# AnalogDiscoveryJacks.net
KiCad netlist of a schematic drawn in EAGLE
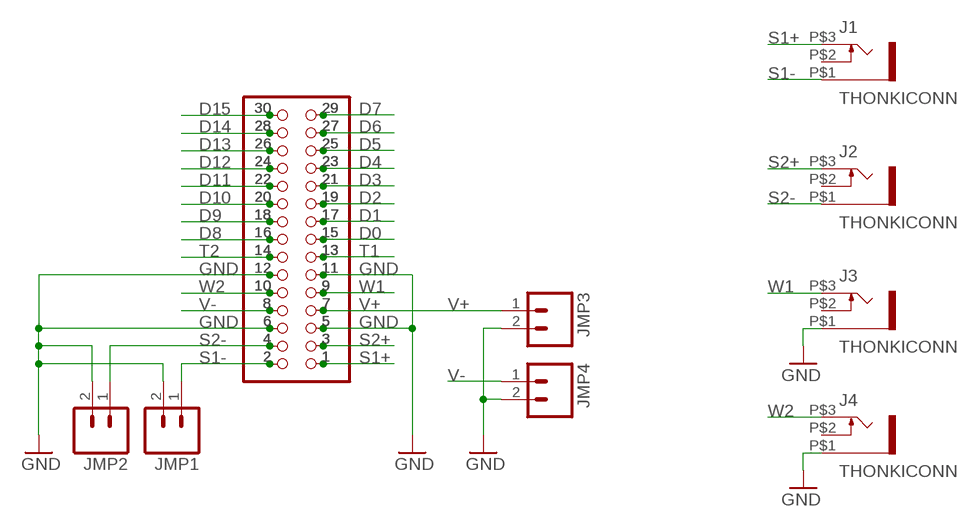
[diagram p0: schematic, sheet 1]

(export (version "E")
  (design (tool "Eeschema 10.0.6"))
  (components
    (comp (ref "J1")
      (value "THONKICONN")
      (footprint "eagle-import:THONKICONN")
      (libsource (lib "eagle-import") (part "THONKICONN"))
    )
    (comp (ref "J2")
      (value "THONKICONN")
      (footprint "eagle-import:THONKICONN")
      (libsource (lib "eagle-import") (part "THONKICONN"))
    )
    (comp (ref "J3")
      (value "THONKICONN")
      (footprint "eagle-import:THONKICONN")
      (libsource (lib "eagle-import") (part "THONKICONN"))
    )
    (comp (ref "J4")
      (value "THONKICONN")
      (footprint "eagle-import:THONKICONN")
      (libsource (lib "eagle-import") (part "THONKICONN"))
    )
    (comp (ref "JMP1")
      (value "M02PTH")
      (footprint "eagle-import:1X02")
      (libsource (lib "eagle-import") (part "M02PTH"))
    )
    (comp (ref "JMP2")
      (value "M02PTH")
      (footprint "eagle-import:1X02")
      (libsource (lib "eagle-import") (part "M02PTH"))
    )
    (comp (ref "JMP3")
      (value "M02PTH")
      (footprint "eagle-import:1X02")
      (libsource (lib "eagle-import") (part "M02PTH"))
    )
    (comp (ref "JMP4")
      (value "M02PTH")
      (footprint "eagle-import:1X02")
      (libsource (lib "eagle-import") (part "M02PTH"))
    )
    (comp (ref "JP1")
      (value "PINHD-2X15")
      (footprint "eagle-import:2X15")
      (libsource (lib "eagle-import") (part "PINHD-2X15"))
    )
    (comp (ref "JP2")
      (value "PINHD-2X15")
      (footprint "eagle-import:2X15")
      (libsource (lib "eagle-import") (part "PINHD-2X15"))
    )
    (comp (ref "JP3")
      (value "PINHD-2X15")
      (footprint "eagle-import:2X15")
      (libsource (lib "eagle-import") (part "PINHD-2X15"))
    )
  )
  (nets
    (net (code "1") (name "/D0") (class "Default")
      (node (ref "JP1") (pin "15") (pinfunction "15_15") (pintype "passive"))
      (node (ref "JP2") (pin "15") (pinfunction "15_15") (pintype "passive"))
      (node (ref "JP3") (pin "15") (pinfunction "15_15") (pintype "passive"))
    )
    (net (code "2") (name "/D1") (class "Default")
      (node (ref "JP1") (pin "17") (pinfunction "17_17") (pintype "passive"))
      (node (ref "JP2") (pin "17") (pinfunction "17_17") (pintype "passive"))
      (node (ref "JP3") (pin "17") (pinfunction "17_17") (pintype "passive"))
    )
    (net (code "3") (name "/D2") (class "Default")
      (node (ref "JP1") (pin "19") (pinfunction "19_19") (pintype "passive"))
      (node (ref "JP2") (pin "19") (pinfunction "19_19") (pintype "passive"))
      (node (ref "JP3") (pin "19") (pinfunction "19_19") (pintype "passive"))
    )
    (net (code "4") (name "/D3") (class "Default")
      (node (ref "JP1") (pin "21") (pinfunction "21_21") (pintype "passive"))
      (node (ref "JP2") (pin "21") (pinfunction "21_21") (pintype "passive"))
      (node (ref "JP3") (pin "21") (pinfunction "21_21") (pintype "passive"))
    )
    (net (code "5") (name "/D4") (class "Default")
      (node (ref "JP1") (pin "23") (pinfunction "23_23") (pintype "passive"))
      (node (ref "JP2") (pin "23") (pinfunction "23_23") (pintype "passive"))
      (node (ref "JP3") (pin "23") (pinfunction "23_23") (pintype "passive"))
    )
    (net (code "6") (name "/D5") (class "Default")
      (node (ref "JP1") (pin "25") (pinfunction "25_25") (pintype "passive"))
      (node (ref "JP2") (pin "25") (pinfunction "25_25") (pintype "passive"))
      (node (ref "JP3") (pin "25") (pinfunction "25_25") (pintype "passive"))
    )
    (net (code "7") (name "/D6") (class "Default")
      (node (ref "JP1") (pin "27") (pinfunction "27_27") (pintype "passive"))
      (node (ref "JP2") (pin "27") (pinfunction "27_27") (pintype "passive"))
      (node (ref "JP3") (pin "27") (pinfunction "27_27") (pintype "passive"))
    )
    (net (code "8") (name "/D7") (class "Default")
      (node (ref "JP1") (pin "29") (pinfunction "29_29") (pintype "passive"))
      (node (ref "JP2") (pin "29") (pinfunction "29_29") (pintype "passive"))
      (node (ref "JP3") (pin "29") (pinfunction "29_29") (pintype "passive"))
    )
    (net (code "9") (name "/D8") (class "Default")
      (node (ref "JP1") (pin "16") (pinfunction "16_16") (pintype "passive"))
      (node (ref "JP2") (pin "16") (pinfunction "16_16") (pintype "passive"))
      (node (ref "JP3") (pin "16") (pinfunction "16_16") (pintype "passive"))
    )
    (net (code "10") (name "/D9") (class "Default")
      (node (ref "JP1") (pin "18") (pinfunction "18_18") (pintype "passive"))
      (node (ref "JP2") (pin "18") (pinfunction "18_18") (pintype "passive"))
      (node (ref "JP3") (pin "18") (pinfunction "18_18") (pintype "passive"))
    )
    (net (code "11") (name "/D10") (class "Default")
      (node (ref "JP1") (pin "20") (pinfunction "20_20") (pintype "passive"))
      (node (ref "JP2") (pin "20") (pinfunction "20_20") (pintype "passive"))
      (node (ref "JP3") (pin "20") (pinfunction "20_20") (pintype "passive"))
    )
    (net (code "12") (name "/D11") (class "Default")
      (node (ref "JP1") (pin "22") (pinfunction "22_22") (pintype "passive"))
      (node (ref "JP2") (pin "22") (pinfunction "22_22") (pintype "passive"))
      (node (ref "JP3") (pin "22") (pinfunction "22_22") (pintype "passive"))
    )
    (net (code "13") (name "/D12") (class "Default")
      (node (ref "JP1") (pin "24") (pinfunction "24_24") (pintype "passive"))
      (node (ref "JP2") (pin "24") (pinfunction "24_24") (pintype "passive"))
      (node (ref "JP3") (pin "24") (pinfunction "24_24") (pintype "passive"))
    )
    (net (code "14") (name "/D13") (class "Default")
      (node (ref "JP1") (pin "26") (pinfunction "26_26") (pintype "passive"))
      (node (ref "JP2") (pin "26") (pinfunction "26_26") (pintype "passive"))
      (node (ref "JP3") (pin "26") (pinfunction "26_26") (pintype "passive"))
    )
    (net (code "15") (name "/D14") (class "Default")
      (node (ref "JP1") (pin "28") (pinfunction "28_28") (pintype "passive"))
      (node (ref "JP2") (pin "28") (pinfunction "28_28") (pintype "passive"))
      (node (ref "JP3") (pin "28") (pinfunction "28_28") (pintype "passive"))
    )
    (net (code "16") (name "/D15") (class "Default")
      (node (ref "JP1") (pin "30") (pinfunction "30_30") (pintype "passive"))
      (node (ref "JP2") (pin "30") (pinfunction "30_30") (pintype "passive"))
      (node (ref "JP3") (pin "30") (pinfunction "30_30") (pintype "passive"))
    )
    (net (code "17") (name "/S1+") (class "Default")
      (node (ref "J1") (pin "P$3") (pinfunction "3_P$3") (pintype "passive"))
      (node (ref "JP1") (pin "1") (pinfunction "1_1") (pintype "passive"))
      (node (ref "JP2") (pin "1") (pinfunction "1_1") (pintype "passive"))
      (node (ref "JP3") (pin "1") (pinfunction "1_1") (pintype "passive"))
    )
    (net (code "18") (name "/S1-") (class "Default")
      (node (ref "J1") (pin "P$1") (pinfunction "5_P$1") (pintype "passive"))
      (node (ref "JMP1") (pin "1") (pinfunction "1_1") (pintype "passive"))
      (node (ref "JP1") (pin "2") (pinfunction "2_2") (pintype "passive"))
      (node (ref "JP2") (pin "2") (pinfunction "2_2") (pintype "passive"))
      (node (ref "JP3") (pin "2") (pinfunction "2_2") (pintype "passive"))
    )
    (net (code "19") (name "/S2+") (class "Default")
      (node (ref "J2") (pin "P$3") (pinfunction "3_P$3") (pintype "passive"))
      (node (ref "JP1") (pin "3") (pinfunction "3_3") (pintype "passive"))
      (node (ref "JP2") (pin "3") (pinfunction "3_3") (pintype "passive"))
      (node (ref "JP3") (pin "3") (pinfunction "3_3") (pintype "passive"))
    )
    (net (code "20") (name "/S2-") (class "Default")
      (node (ref "J2") (pin "P$1") (pinfunction "5_P$1") (pintype "passive"))
      (node (ref "JMP2") (pin "1") (pinfunction "1_1") (pintype "passive"))
      (node (ref "JP1") (pin "4") (pinfunction "4_4") (pintype "passive"))
      (node (ref "JP2") (pin "4") (pinfunction "4_4") (pintype "passive"))
      (node (ref "JP3") (pin "4") (pinfunction "4_4") (pintype "passive"))
    )
    (net (code "21") (name "/T1") (class "Default")
      (node (ref "JP1") (pin "13") (pinfunction "13_13") (pintype "passive"))
      (node (ref "JP2") (pin "13") (pinfunction "13_13") (pintype "passive"))
      (node (ref "JP3") (pin "13") (pinfunction "13_13") (pintype "passive"))
    )
    (net (code "22") (name "/T2") (class "Default")
      (node (ref "JP1") (pin "14") (pinfunction "14_14") (pintype "passive"))
      (node (ref "JP2") (pin "14") (pinfunction "14_14") (pintype "passive"))
      (node (ref "JP3") (pin "14") (pinfunction "14_14") (pintype "passive"))
    )
    (net (code "23") (name "/V+") (class "Default")
      (node (ref "JMP3") (pin "1") (pinfunction "1_1") (pintype "passive"))
      (node (ref "JP1") (pin "7") (pinfunction "7_7") (pintype "passive"))
      (node (ref "JP2") (pin "7") (pinfunction "7_7") (pintype "passive"))
      (node (ref "JP3") (pin "7") (pinfunction "7_7") (pintype "passive"))
    )
    (net (code "24") (name "/V-") (class "Default")
      (node (ref "JMP4") (pin "1") (pinfunction "1_1") (pintype "passive"))
      (node (ref "JP1") (pin "8") (pinfunction "8_8") (pintype "passive"))
      (node (ref "JP2") (pin "8") (pinfunction "8_8") (pintype "passive"))
      (node (ref "JP3") (pin "8") (pinfunction "8_8") (pintype "passive"))
    )
    (net (code "25") (name "/W1") (class "Default")
      (node (ref "J3") (pin "P$3") (pinfunction "3_P$3") (pintype "passive"))
      (node (ref "JP1") (pin "9") (pinfunction "9_9") (pintype "passive"))
      (node (ref "JP2") (pin "9") (pinfunction "9_9") (pintype "passive"))
      (node (ref "JP3") (pin "9") (pinfunction "9_9") (pintype "passive"))
    )
    (net (code "26") (name "/W2") (class "Default")
      (node (ref "J4") (pin "P$3") (pinfunction "3_P$3") (pintype "passive"))
      (node (ref "JP1") (pin "10") (pinfunction "10_10") (pintype "passive"))
      (node (ref "JP2") (pin "10") (pinfunction "10_10") (pintype "passive"))
      (node (ref "JP3") (pin "10") (pinfunction "10_10") (pintype "passive"))
    )
    (net (code "27") (name "GND") (class "Default")
      (node (ref "J3") (pin "P$1") (pinfunction "5_P$1") (pintype "passive"))
      (node (ref "J4") (pin "P$1") (pinfunction "5_P$1") (pintype "passive"))
      (node (ref "JMP1") (pin "2") (pinfunction "2_2") (pintype "passive"))
      (node (ref "JMP2") (pin "2") (pinfunction "2_2") (pintype "passive"))
      (node (ref "JMP3") (pin "2") (pinfunction "2_2") (pintype "passive"))
      (node (ref "JMP4") (pin "2") (pinfunction "2_2") (pintype "passive"))
      (node (ref "JP1") (pin "11") (pinfunction "11_11") (pintype "passive"))
      (node (ref "JP1") (pin "12") (pinfunction "12_12") (pintype "passive"))
      (node (ref "JP1") (pin "5") (pinfunction "5_5") (pintype "passive"))
      (node (ref "JP1") (pin "6") (pinfunction "6_6") (pintype "passive"))
      (node (ref "JP2") (pin "11") (pinfunction "11_11") (pintype "passive"))
      (node (ref "JP2") (pin "12") (pinfunction "12_12") (pintype "passive"))
      (node (ref "JP2") (pin "5") (pinfunction "5_5") (pintype "passive"))
      (node (ref "JP2") (pin "6") (pinfunction "6_6") (pintype "passive"))
      (node (ref "JP3") (pin "11") (pinfunction "11_11") (pintype "passive"))
      (node (ref "JP3") (pin "12") (pinfunction "12_12") (pintype "passive"))
      (node (ref "JP3") (pin "5") (pinfunction "5_5") (pintype "passive"))
      (node (ref "JP3") (pin "6") (pinfunction "6_6") (pintype "passive"))
    )
    (net (code "28") (name "unconnected-(J1-4-PadP$2)") (class "Default")
      (node (ref "J1") (pin "P$2") (pinfunction "4_P$2") (pintype "passive"))
    )
    (net (code "29") (name "unconnected-(J2-4-PadP$2)") (class "Default")
      (node (ref "J2") (pin "P$2") (pinfunction "4_P$2") (pintype "passive"))
    )
    (net (code "30") (name "unconnected-(J3-4-PadP$2)") (class "Default")
      (node (ref "J3") (pin "P$2") (pinfunction "4_P$2") (pintype "passive"))
    )
    (net (code "31") (name "unconnected-(J4-4-PadP$2)") (class "Default")
      (node (ref "J4") (pin "P$2") (pinfunction "4_P$2") (pintype "passive"))
    )
  )
)
